# Power_Menegament.net
KiCad netlist of a schematic drawn in Altium Designer
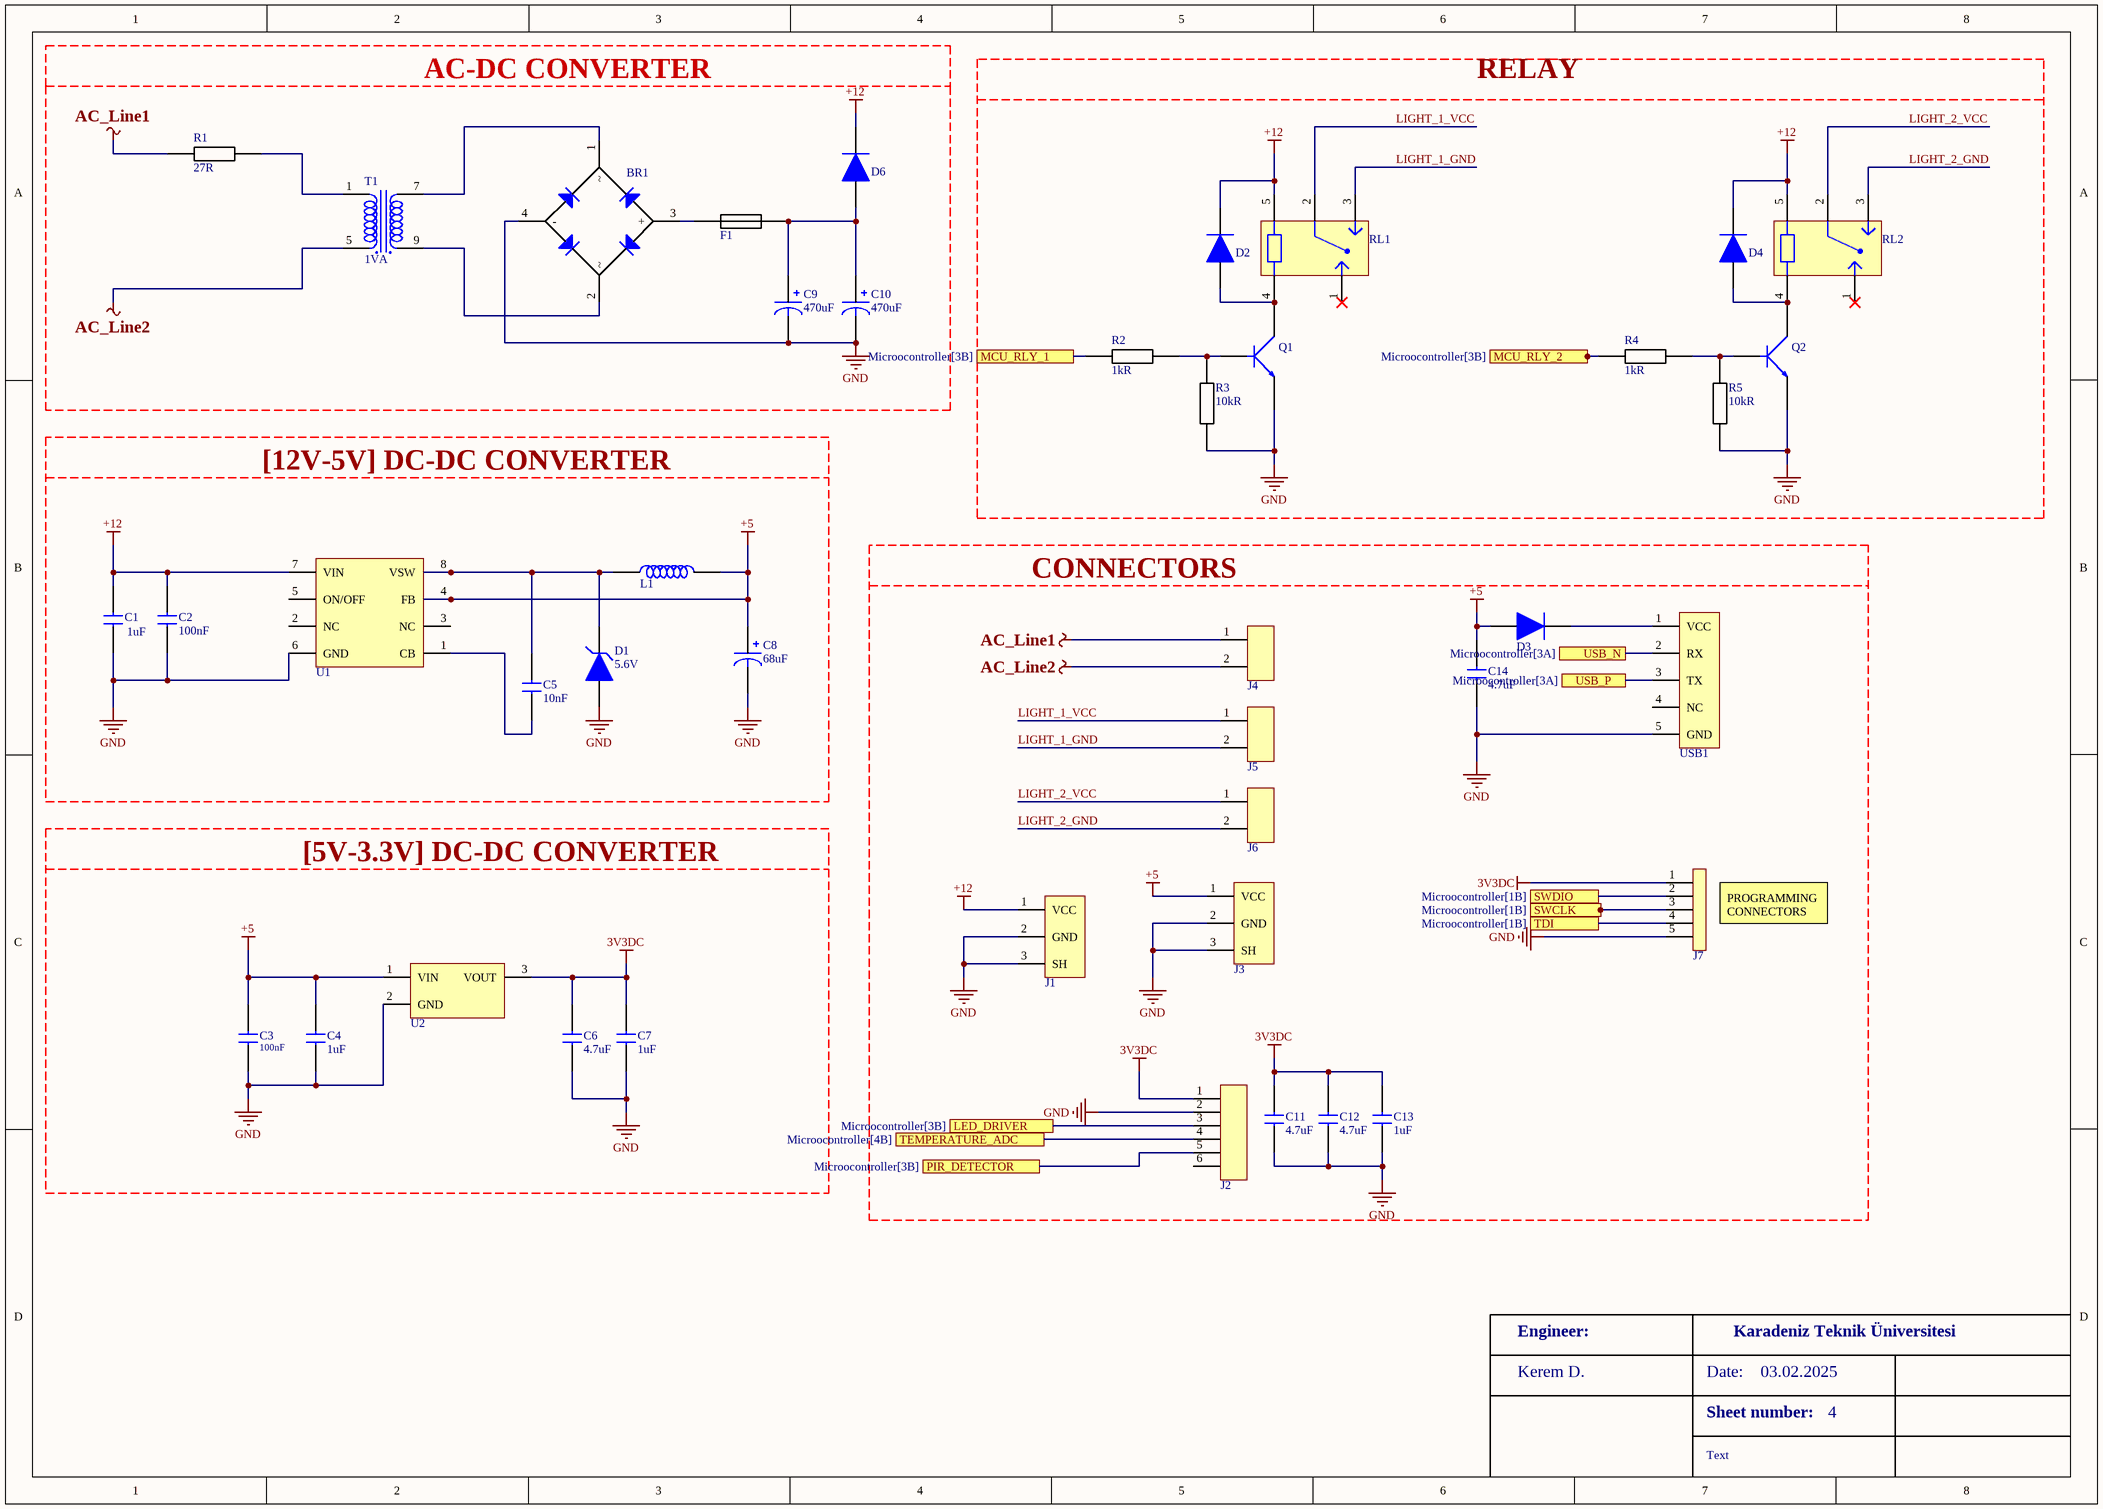
[diagram p0: Power Menegament.SchDoc]

(export (version "E")
  (design (tool "Eeschema 10.0.6"))
  (components
    (comp (ref "BR1")
      (value "DB105STR")
      (footprint "DB105STR")
      (description "Bridge Rect 1PHASE 600V 1A Db-s")
      (fields
        (field (name "MANUFACTURER") "Sangdest Microelectronics")
        (field (name "MANUFACTURER PART NUMBER") "DB105S")
        (field (name "DESIGNED BY") "Kerem")
      )
      (libsource (lib "library") (part "DB105STR"))
    )
    (comp (ref "C1")
      (value "1uF")
      (footprint "CAP_0805")
      (description "Cap CER, 1uF, 16V, 0805;")
      (fields
        (field (name "MANUFACTURER") "KEMET")
        (field (name "MANUFACTURER PART NUMBER") "CHA08C105K4RXL7189")
        (field (name "DESIGNED BY") "Kerem")
      )
      (libsource (lib "library") (part "CAP_CER_1uF_0805"))
    )
    (comp (ref "C2")
      (value "100nF")
      (footprint "CAP_0805")
      (description "Ceramic Capacitor,50V, %10, 0.1uF, Surface Mount, 0805")
      (fields
        (field (name "MANUFACTURER") "Samsung")
        (field (name "MANUFACTURER PART NUMBER") "CL21B104KBCNNNC")
        (field (name "DESIGNED BY") "Kerem")
      )
      (libsource (lib "library") (part "CAP_CER_100nF_0805"))
    )
    (comp (ref "C3")
      (value "100nF")
      (footprint "CAP_0603")
      (description "0.1 µF ±20% 50V Ceramic Capacitor X7R 0603 (1608 Metric)")
      (fields
        (field (name "MANUFACTURER") "KEMET")
        (field (name "MANUFACTURER PART NUMBER") "C0603C104M5RACTU")
      )
      (libsource (lib "library") (part "CAP CER 100nF 0603"))
    )
    (comp (ref "C4")
      (value "1uF")
      (footprint "CAP_0805")
      (description "Cap CER, 1uF, 16V, 0805;")
      (fields
        (field (name "MANUFACTURER") "KEMET")
        (field (name "MANUFACTURER PART NUMBER") "CHA08C105K4RXL7189")
        (field (name "DESIGNED BY") "Kerem")
      )
      (libsource (lib "library") (part "CAP_CER_1uF_0805"))
    )
    (comp (ref "C5")
      (value "10nF")
      (footprint "CAP_0603")
      (description "Ceramic Capacitor,16V, 10%, 0.01uF, Surface Mount, 0603")
      (fields
        (field (name "MANUFACTURER") "Walsin Technologies")
        (field (name "MANUFACTURER PART NUMBER") "0603B103K160CT")
        (field (name "DESIGNED BY") "Kerem")
      )
      (libsource (lib "library") (part "CAP_CER_10nF_0603"))
    )
    (comp (ref "C6")
      (value "4.7uF")
      (footprint "CAP_0805")
      (description "CAP CER 4.7uF,%10, Surface Mount, 0805")
      (fields
        (field (name "MANUFACTURER") "Samsung")
        (field (name "MANUFACTURER PART NUMBER") "CL21A475KAQNNNE")
        (field (name "DESIGNED BY") "Kerem")
      )
      (libsource (lib "library") (part "CAP_CER_4.7uF_0805"))
    )
    (comp (ref "C7")
      (value "1uF")
      (footprint "CAP_0805")
      (description "Cap CER, 1uF, 16V, 0805;")
      (fields
        (field (name "MANUFACTURER") "KEMET")
        (field (name "MANUFACTURER PART NUMBER") "CHA08C105K4RXL7189")
        (field (name "DESIGNED BY") "Kerem")
      )
      (libsource (lib "library") (part "CAP_CER_1uF_0805"))
    )
    (comp (ref "C8")
      (value "68uF")
      (footprint "CAP EEVSERİES")
      (description "Aluminum Electrolytic Capacitor, 35V, 20%, 68uF, Surface Mount, 2626")
      (fields
        (field (name "MANUFACTURER") "KEMET")
        (field (name "MANUFACTURER PART NUMBER") "EEV686M035A9HAA")
        (field (name "DESIGNED BY") "Kerem")
      )
      (libsource (lib "library") (part "CAP_ALU_68uF"))
    )
    (comp (ref "C9")
      (value "470uF")
      (footprint "CAP_RADİAL_D10_R5")
      (fields
        (field (name "MANUFACTURER") "KEMET")
        (field (name "MANUFACTURER PART NUMBER") "ESH477M035AH4AA")
        (field (name "DESIGNED BY") "Kerem")
      )
      (libsource (lib "library") (part "CAP_ALU_470uF"))
    )
    (comp (ref "C10")
      (value "470uF")
      (footprint "CAP_RADİAL_D10_R5")
      (fields
        (field (name "MANUFACTURER") "KEMET")
        (field (name "MANUFACTURER PART NUMBER") "ESH477M035AH4AA")
        (field (name "DESIGNED BY") "Kerem")
      )
      (libsource (lib "library") (part "CAP_ALU_470uF"))
    )
    (comp (ref "C11")
      (value "4.7uF")
      (footprint "CAP_0805")
      (description "CAP CER 4.7uF,%10, Surface Mount, 0805")
      (fields
        (field (name "MANUFACTURER") "Samsung")
        (field (name "MANUFACTURER PART NUMBER") "CL21A475KAQNNNE")
        (field (name "DESIGNED BY") "Kerem")
      )
      (libsource (lib "library") (part "CAP_CER_4.7uF_0805"))
    )
    (comp (ref "C12")
      (value "4.7uF")
      (footprint "CAP_0805")
      (description "CAP CER 4.7uF,%10, Surface Mount, 0805")
      (fields
        (field (name "MANUFACTURER") "Samsung")
        (field (name "MANUFACTURER PART NUMBER") "CL21A475KAQNNNE")
        (field (name "DESIGNED BY") "Kerem")
      )
      (libsource (lib "library") (part "CAP_CER_4.7uF_0805"))
    )
    (comp (ref "C13")
      (value "1uF")
      (footprint "CAP_0805")
      (description "Cap CER, 1uF, 16V, 0805;")
      (fields
        (field (name "MANUFACTURER") "KEMET")
        (field (name "MANUFACTURER PART NUMBER") "CHA08C105K4RXL7189")
        (field (name "DESIGNED BY") "Kerem")
      )
      (libsource (lib "library") (part "CAP_CER_1uF_0805"))
    )
    (comp (ref "C14")
      (value "4.7uF")
      (footprint "CAP_0805")
      (description "CAP CER 4.7uF,%10, Surface Mount, 0805")
      (fields
        (field (name "MANUFACTURER") "Samsung")
        (field (name "MANUFACTURER PART NUMBER") "CL21A475KAQNNNE")
        (field (name "DESIGNED BY") "Kerem")
      )
      (libsource (lib "library") (part "CAP_CER_4.7uF_0805"))
    )
    (comp (ref "D1")
      (value "1SMB5919BT3G")
      (footprint "SMB")
      (description "Zener Diode, 5.6V V(Z), 5%, 0.55W, Silicon, Unidirectional, DO-214AA")
      (fields
        (field (name "MANUFACTURER") "ON Semiconductor")
        (field (name "REFERENCE VOLTAGE-NOM") "5.6V")
        (field (name "DESIGNED BY") "Kerem")
      )
      (libsource (lib "library") (part "1SMB5919BT3G"))
    )
    (comp (ref "D2")
      (value "1N4148WS")
      (footprint "SOD323F")
      (description "Rectifier Diode, 1 Phase, 1 Element, 0.15A, 100V V(RRM), Silicon")
      (fields
        (field (name "MANUFACTURER") "ON Semiconductor / Fairchild")
        (field (name "DESIGNED BY") "Kerem")
      )
      (libsource (lib "library") (part "1N4148WS"))
    )
    (comp (ref "D3")
      (value "1N4148WS")
      (footprint "SOD323F")
      (description "Rectifier Diode, 1 Phase, 1 Element, 0.15A, 100V V(RRM), Silicon")
      (fields
        (field (name "MANUFACTURER") "ON Semiconductor / Fairchild")
        (field (name "DESIGNED BY") "Kerem")
      )
      (libsource (lib "library") (part "1N4148WS"))
    )
    (comp (ref "D4")
      (value "1N4148WS")
      (footprint "SOD323F")
      (description "Rectifier Diode, 1 Phase, 1 Element, 0.15A, 100V V(RRM), Silicon")
      (fields
        (field (name "MANUFACTURER") "ON Semiconductor / Fairchild")
        (field (name "DESIGNED BY") "Kerem")
      )
      (libsource (lib "library") (part "1N4148WS"))
    )
    (comp (ref "D6")
      (value "1N4148WS")
      (footprint "SOD323F")
      (description "Rectifier Diode, 1 Phase, 1 Element, 0.15A, 100V V(RRM), Silicon")
      (fields
        (field (name "MANUFACTURER") "ON Semiconductor / Fairchild")
        (field (name "DESIGNED BY") "Kerem")
      )
      (libsource (lib "library") (part "1N4148WS"))
    )
    (comp (ref "F1")
      (value "3413.0216.22")
      (footprint "FUSE 3413.0216.22")
      (description "Electric Fuse, Very Fast Blow, 1A, 32VAC, 63VDC, 63A (IR), Surface Mount, 1206")
      (fields (field (name "MANUFACTURER") "Schurter") (field (name "DESIGNED BY") "Kerem"))
      (libsource (lib "library") (part "FUSE 3413.0216.22"))
    )
    (comp (ref "J1")
      (value "JACK")
      (footprint "JACK")
      (description "DC Power Plug or Jack")
      (fields
        (field (name "MANUFACTURER") "CUI")
        (field (name "MANUFACTURER PART NUMBER") "PJ-037AH-SMT-TR")
        (field (name "DESIGNED BY") "Kerem")
      )
      (libsource (lib "library") (part "PJ-037AH-SMT-TR"))
    )
    (comp (ref "J2")
      (value "64800611622")
      (footprint "64800611622")
      (description "WR-WTB Wire-to-Board Connectors 1.50 mm")
      (fields (field (name "MANUFACTURER") "Wurth Electronics") (field (name "DESIGNED BY") "Kerem"))
      (libsource (lib "library") (part "64800611622_CONN_6PINS"))
    )
    (comp (ref "J3")
      (value "JACK")
      (footprint "JACK")
      (description "DC Power Plug or Jack")
      (fields
        (field (name "MANUFACTURER") "CUI")
        (field (name "MANUFACTURER PART NUMBER") "PJ-037AH-SMT-TR")
        (field (name "DESIGNED BY") "Kerem")
      )
      (libsource (lib "library") (part "PJ-037AH-SMT-TR"))
    )
    (comp (ref "J4")
      (value "JACK")
      (footprint "TBP01R1-508")
      (description "Strip Terminal Block 2 Pins")
      (fields
        (field (name "MANUFACTURER") "CUI Devices")
        (field (name "MANUFACTURER PART NUMBER") "TBP01R1-508-02BE")
        (field (name "DESIGNED BY") "Kerem")
      )
      (libsource (lib "library") (part "TBP01R1-508-02BE"))
    )
    (comp (ref "J5")
      (value "JACK")
      (footprint "TBP01R1-508")
      (description "Strip Terminal Block 2 Pins")
      (fields
        (field (name "MANUFACTURER") "CUI Devices")
        (field (name "MANUFACTURER PART NUMBER") "TBP01R1-508-02BE")
        (field (name "DESIGNED BY") "Kerem")
      )
      (libsource (lib "library") (part "TBP01R1-508-02BE"))
    )
    (comp (ref "J6")
      (value "JACK")
      (footprint "TBP01R1-508")
      (description "Strip Terminal Block 2 Pins")
      (fields
        (field (name "MANUFACTURER") "CUI Devices")
        (field (name "MANUFACTURER PART NUMBER") "TBP01R1-508-02BE")
        (field (name "DESIGNED BY") "Kerem")
      )
      (libsource (lib "library") (part "TBP01R1-508-02BE"))
    )
    (comp (ref "J7")
      (value "SMH-105-02-L-S")
      (footprint "PINHEADER1X5_RA")
      (description "Board Connector, 5 Contact(s), Socket")
      (fields (field (name "MANUFACTURER") "Samtec") (field (name "DESIGNED BY") "Kerem"))
      (libsource (lib "library") (part "SMH-105-02-L-S"))
    )
    (comp (ref "L1")
      (value "78438335470")
      (footprint "SMB")
      (description "General Purpose Inductor, 47uH, 20%, 1 Element, Iron Alloy-Core, SMD, 1212")
      (fields (field (name "MANUFACTURER") "Wurth Electronics") (field (name "DESIGNED BY") "Kerem"))
      (libsource (lib "library") (part "IND_47uH"))
    )
    (comp (ref "Q1")
      (value "MMBT3904-7-F")
      (footprint "SOT-23F")
      (description "Small Signal Bipolar Transistor, 0.2A I(C), 40V V(BR)CEO, 1-Element, NPN, Silicon")
      (fields (field (name "MANUFACTURER") "Diodes Zetex") (field (name "DESIGNED BY") "Kerem"))
      (libsource (lib "library") (part "MMBT3904-7-F"))
    )
    (comp (ref "Q2")
      (value "MMBT3904-7-F")
      (footprint "SOT-23F")
      (description "Small Signal Bipolar Transistor, 0.2A I(C), 40V V(BR)CEO, 1-Element, NPN, Silicon")
      (fields (field (name "MANUFACTURER") "Diodes Zetex") (field (name "DESIGNED BY") "Kerem"))
      (libsource (lib "library") (part "MMBT3904-7-F"))
    )
    (comp (ref "R1")
      (value "27R")
      (footprint "RES_AXIAL_W")
      (description "5W, 27ohm, 350V, 5% Through Hole Mount, 8739")
      (fields
        (field (name "MANUFACTURER") "TE Connectivity CGS")
        (field (name "MANUFACTURER PART NUMBER") "SQPW527RJ")
        (field (name "DESIGNED BY") "Kerem")
      )
      (libsource (lib "library") (part "5WD27"))
    )
    (comp (ref "R2")
      (value "1kR")
      (footprint "RES_0603")
      (description "0.1W, 1000ohm, 75V, 5%, Surface Mount, 0603")
      (fields
        (field (name "MANUFACTURER") "Yageo")
        (field (name "MANUFACTURER PART NUMBER") "RC0603JR-071KL")
        (field (name "DESIGNED BY") "Kerem")
      )
      (libsource (lib "library") (part "RES_1K OHM_0603"))
    )
    (comp (ref "R3")
      (value "10kR")
      (footprint "RES_0603")
      (fields
        (field (name "MANUFACTURER") "Yageo")
        (field (name "MANUFACTURER PART NUMBER") "RC0603FR-0710KL")
        (field (name "TOLERANCE") "1%")
        (field (name "DESIGNED BY") "Kerem")
      )
      (libsource (lib "library") (part "RES 10K OHM 0603"))
    )
    (comp (ref "R4")
      (value "1kR")
      (footprint "RES_0603")
      (description "0.1W, 1000ohm, 75V, 5%, Surface Mount, 0603")
      (fields
        (field (name "MANUFACTURER") "Yageo")
        (field (name "MANUFACTURER PART NUMBER") "RC0603JR-071KL")
        (field (name "DESIGNED BY") "Kerem")
      )
      (libsource (lib "library") (part "RES_1K OHM_0603"))
    )
    (comp (ref "R5")
      (value "10kR")
      (footprint "RES_0603")
      (fields
        (field (name "MANUFACTURER") "Yageo")
        (field (name "MANUFACTURER PART NUMBER") "RC0603FR-0710KL")
        (field (name "TOLERANCE") "1%")
        (field (name "DESIGNED BY") "Kerem")
      )
      (libsource (lib "library") (part "RES 10K OHM 0603"))
    )
    (comp (ref "RL1")
      (value "ALQ112")
      (footprint "ALQ112")
      (fields (field (name "MANUFACTURER") "Panasonic") (field (name "DESIGNED BY") "Kerem"))
      (libsource (lib "library") (part "ALQ112"))
    )
    (comp (ref "RL2")
      (value "ALQ112")
      (footprint "ALQ112")
      (fields (field (name "MANUFACTURER") "Panasonic") (field (name "DESIGNED BY") "Kerem"))
      (libsource (lib "library") (part "ALQ112"))
    )
    (comp (ref "T1")
      (value "BV302S12010-ZU")
      (footprint "BV302S12010-ZU")
      (description "Split Bobbin Power Transformer, 1VA")
      (fields
        (field (name "MANUFACTURER") "Zettler Magnetics")
        (field (name "MANUFACTURER PART NUMBER") "BV302S12010")
        (field (name "POWER - MAX") "1VA")
        (field (name "DESIGNED BY") "Kerem")
      )
      (libsource (lib "library") (part "BV302S12010-ZU"))
    )
    (comp (ref "U1")
      (value "LM2675MX-12/NOPB")
      (footprint "SOIC8")
      (description "Switching Regulator, Voltage-mode, 2.2A, 275kHz Switching Freq-Max, DMOS, PDSO8")
      (fields (field (name "MANUFACTURER") "TI National Semiconductor") (field (name "DESIGNED BY") "Kerem"))
      (libsource (lib "library") (part "LM2675MX-12/NOPB"))
    )
    (comp (ref "U2")
      (value "AP7361-33E-13")
      (footprint "SOT223")
      (description "Fixed Positive LDO Regulator, 3.3V, 0.7V Dropout, CMOS, PSSO3")
      (fields (field (name "MANUFACTURER") "Diodes") (field (name "DESIGNED BY") "Kerem"))
      (libsource (lib "library") (part "AP7361-33E-13"))
    )
    (comp (ref "USB1")
      (value "10118192-0001LF")
      (footprint "Micro_B_USB")
      (description "CONN USB MICRO B RECPT SMT R/A")
      (fields (field (name "MANUFACTURER") "Amphenol ICC / FCI") (field (name "DESIGNED BY") "Kerem"))
      (libsource (lib "library") (part "Micro B USB Connector"))
    )
  )
  (nets
    (net (code "1") (name "+5") (class "Default")
      (node (ref "C14") (pin "2") (pinfunction "2_2") (pintype "passive"))
      (node (ref "C3") (pin "2") (pinfunction "2_2") (pintype "passive"))
      (node (ref "C4") (pin "2") (pinfunction "2_2") (pintype "passive"))
      (node (ref "C8") (pin "1") (pinfunction "1_1") (pintype "passive"))
      (node (ref "D3") (pin "2") (pinfunction "2_2") (pintype "passive"))
      (node (ref "J3") (pin "1") (pinfunction "VCC_1") (pintype "power_in"))
      (node (ref "L1") (pin "2") (pinfunction "2_2") (pintype "passive"))
      (node (ref "U1") (pin "4") (pinfunction "FB_4") (pintype "passive"))
      (node (ref "U2") (pin "1") (pinfunction "VIN_1") (pintype "passive"))
    )
    (net (code "2") (name "+12") (class "Default")
      (node (ref "C1") (pin "2") (pinfunction "2_2") (pintype "passive"))
      (node (ref "C2") (pin "2") (pinfunction "2_2") (pintype "passive"))
      (node (ref "D2") (pin "1") (pinfunction "1_1") (pintype "passive"))
      (node (ref "D4") (pin "1") (pinfunction "1_1") (pintype "passive"))
      (node (ref "D6") (pin "1") (pinfunction "1_1") (pintype "passive"))
      (node (ref "J1") (pin "1") (pinfunction "VCC_1") (pintype "power_in"))
      (node (ref "RL1") (pin "5") (pintype "passive"))
      (node (ref "RL2") (pin "5") (pintype "passive"))
      (node (ref "U1") (pin "7") (pinfunction "VIN_7") (pintype "passive"))
    )
    (net (code "4") (name "/LED_DRIVER") (class "Default")
      (node (ref "J2") (pin "3") (pinfunction "3_3") (pintype "passive"))
    )
    (net (code "5") (name "/LIGHT_1_GND") (class "Default")
      (node (ref "J5") (pin "2") (pinfunction "2_2") (pintype "power_in"))
      (node (ref "RL1") (pin "3") (pintype "passive"))
    )
    (net (code "6") (name "/LIGHT_1_VCC") (class "Default")
      (node (ref "J5") (pin "1") (pinfunction "1_1") (pintype "power_in"))
      (node (ref "RL1") (pin "2") (pintype "passive"))
    )
    (net (code "7") (name "/LIGHT_2_GND") (class "Default")
      (node (ref "J6") (pin "2") (pinfunction "2_2") (pintype "power_in"))
      (node (ref "RL2") (pin "3") (pintype "passive"))
    )
    (net (code "8") (name "/LIGHT_2_VCC") (class "Default")
      (node (ref "J6") (pin "1") (pinfunction "1_1") (pintype "power_in"))
      (node (ref "RL2") (pin "2") (pintype "passive"))
    )
    (net (code "9") (name "/MCU_RLY_1") (class "Default")
      (node (ref "R2") (pin "1") (pinfunction "1_1") (pintype "passive"))
    )
    (net (code "10") (name "/MCU_RLY_2") (class "Default")
      (node (ref "R4") (pin "1") (pinfunction "1_1") (pintype "passive"))
    )
    (net (code "11") (name "/PIR_DETECTOR") (class "Default")
      (node (ref "J2") (pin "5") (pinfunction "5_5") (pintype "passive"))
    )
    (net (code "12") (name "/SWCLK") (class "Default")
      (node (ref "J7") (pin "3") (pinfunction "3_3") (pintype "power_in"))
    )
    (net (code "13") (name "/SWDIO") (class "Default")
      (node (ref "J7") (pin "2") (pinfunction "2_2") (pintype "power_in"))
    )
    (net (code "14") (name "/TDI") (class "Default")
      (node (ref "J7") (pin "4") (pinfunction "4_4") (pintype "power_in"))
    )
    (net (code "15") (name "/TEMPERATURE_ADC") (class "Default")
      (node (ref "J2") (pin "4") (pinfunction "4_4") (pintype "passive"))
    )
    (net (code "16") (name "/USB_N") (class "Default")
      (node (ref "USB1") (pin "2") (pinfunction "RX_2") (pintype "passive"))
    )
    (net (code "17") (name "/USB_P") (class "Default")
      (node (ref "USB1") (pin "3") (pinfunction "TX_3") (pintype "passive"))
    )
    (net (code "18") (name "3V3DC") (class "Default")
      (node (ref "C11") (pin "2") (pinfunction "2_2") (pintype "passive"))
      (node (ref "C12") (pin "2") (pinfunction "2_2") (pintype "passive"))
      (node (ref "C13") (pin "2") (pinfunction "2_2") (pintype "passive"))
      (node (ref "C6") (pin "2") (pinfunction "2_2") (pintype "passive"))
      (node (ref "C7") (pin "2") (pinfunction "2_2") (pintype "passive"))
      (node (ref "J2") (pin "1") (pinfunction "1_1") (pintype "passive"))
      (node (ref "J7") (pin "1") (pinfunction "1_1") (pintype "power_in"))
      (node (ref "U2") (pin "3") (pinfunction "VOUT_3") (pintype "passive"))
    )
    (net (code "19") (name "AC_Line1") (class "Default")
      (node (ref "J4") (pin "1") (pinfunction "1_1") (pintype "power_in"))
      (node (ref "R1") (pin "1") (pinfunction "1_1") (pintype "passive"))
    )
    (net (code "20") (name "AC_Line2") (class "Default")
      (node (ref "J4") (pin "2") (pinfunction "2_2") (pintype "power_in"))
      (node (ref "T1") (pin "5") (pinfunction "2_5") (pintype "passive"))
    )
    (net (code "21") (name "GND") (class "Default")
      (node (ref "BR1") (pin "4") (pinfunction "-_4") (pintype "passive"))
      (node (ref "C1") (pin "1") (pinfunction "1_1") (pintype "passive"))
      (node (ref "C10") (pin "2") (pinfunction "2_2") (pintype "passive"))
      (node (ref "C11") (pin "1") (pinfunction "1_1") (pintype "passive"))
      (node (ref "C12") (pin "1") (pinfunction "1_1") (pintype "passive"))
      (node (ref "C13") (pin "1") (pinfunction "1_1") (pintype "passive"))
      (node (ref "C14") (pin "1") (pinfunction "1_1") (pintype "passive"))
      (node (ref "C2") (pin "1") (pinfunction "1_1") (pintype "passive"))
      (node (ref "C3") (pin "1") (pinfunction "1_1") (pintype "passive"))
      (node (ref "C4") (pin "1") (pinfunction "1_1") (pintype "passive"))
      (node (ref "C6") (pin "1") (pinfunction "1_1") (pintype "passive"))
      (node (ref "C7") (pin "1") (pinfunction "1_1") (pintype "passive"))
      (node (ref "C8") (pin "2") (pinfunction "2_2") (pintype "passive"))
      (node (ref "C9") (pin "2") (pinfunction "2_2") (pintype "passive"))
      (node (ref "D1") (pin "1") (pinfunction "A_1") (pintype "passive"))
      (node (ref "J1") (pin "2") (pinfunction "GND_2") (pintype "power_in"))
      (node (ref "J1") (pin "3") (pinfunction "SH_3") (pintype "power_in"))
      (node (ref "J2") (pin "2") (pinfunction "2_2") (pintype "passive"))
      (node (ref "J3") (pin "2") (pinfunction "GND_2") (pintype "power_in"))
      (node (ref "J3") (pin "3") (pinfunction "SH_3") (pintype "power_in"))
      (node (ref "J7") (pin "5") (pinfunction "5_5") (pintype "power_in"))
      (node (ref "Q1") (pin "2") (pinfunction "E_2") (pintype "passive"))
      (node (ref "Q2") (pin "2") (pinfunction "E_2") (pintype "passive"))
      (node (ref "R3") (pin "1") (pinfunction "1_1") (pintype "passive"))
      (node (ref "R5") (pin "1") (pinfunction "1_1") (pintype "passive"))
      (node (ref "U1") (pin "6") (pinfunction "GND_6") (pintype "passive"))
      (node (ref "U2") (pin "2") (pinfunction "GND_2") (pintype "passive"))
      (node (ref "USB1") (pin "5") (pinfunction "GND_5") (pintype "passive"))
    )
    (net (code "22") (name "Net-(BR1-+)") (class "Default")
      (node (ref "BR1") (pin "3") (pinfunction "+_3") (pintype "passive"))
      (node (ref "F1") (pin "1") (pinfunction "1_1") (pintype "passive"))
    )
    (net (code "23") (name "Net-(C10-Pad1)") (class "Default")
      (node (ref "C10") (pin "1") (pinfunction "1_1") (pintype "passive"))
      (node (ref "C9") (pin "1") (pinfunction "1_1") (pintype "passive"))
      (node (ref "D6") (pin "2") (pinfunction "2_2") (pintype "passive"))
      (node (ref "F1") (pin "2") (pinfunction "2_2") (pintype "passive"))
    )
    (net (code "24") (name "Net-(D1-C)") (class "Default")
      (node (ref "C5") (pin "2") (pinfunction "2_2") (pintype "passive"))
      (node (ref "D1") (pin "2") (pinfunction "C_2") (pintype "passive"))
      (node (ref "L1") (pin "1") (pinfunction "1_1") (pintype "passive"))
      (node (ref "U1") (pin "8") (pinfunction "VSW_8") (pintype "passive"))
    )
    (net (code "25") (name "Net-(Q1-B)") (class "Default")
      (node (ref "Q1") (pin "1") (pinfunction "B_1") (pintype "passive"))
      (node (ref "R2") (pin "2") (pinfunction "2_2") (pintype "passive"))
      (node (ref "R3") (pin "2") (pinfunction "2_2") (pintype "passive"))
    )
    (net (code "26") (name "Net-(Q1-C)") (class "Default")
      (node (ref "D2") (pin "2") (pinfunction "2_2") (pintype "passive"))
      (node (ref "Q1") (pin "3") (pinfunction "C_3") (pintype "passive"))
      (node (ref "RL1") (pin "4") (pintype "passive"))
    )
    (net (code "27") (name "Net-(Q2-B)") (class "Default")
      (node (ref "Q2") (pin "1") (pinfunction "B_1") (pintype "passive"))
      (node (ref "R4") (pin "2") (pinfunction "2_2") (pintype "passive"))
      (node (ref "R5") (pin "2") (pinfunction "2_2") (pintype "passive"))
    )
    (net (code "28") (name "Net-(Q2-C)") (class "Default")
      (node (ref "D4") (pin "2") (pinfunction "2_2") (pintype "passive"))
      (node (ref "Q2") (pin "3") (pinfunction "C_3") (pintype "passive"))
      (node (ref "RL2") (pin "4") (pintype "passive"))
    )
    (net (code "29") (name "Net-(R1-Pad2)") (class "Default")
      (node (ref "R1") (pin "2") (pinfunction "2_2") (pintype "passive"))
      (node (ref "T1") (pin "1") (pinfunction "1_1") (pintype "passive"))
    )
    (net (code "30") (name "Net-(T1-3)") (class "Default")
      (node (ref "BR1") (pin "1") (pinfunction "~_1") (pintype "passive"))
      (node (ref "T1") (pin "7") (pinfunction "3_7") (pintype "passive"))
    )
    (net (code "31") (name "Net-(T1-4)") (class "Default")
      (node (ref "BR1") (pin "2") (pinfunction "~_2") (pintype "passive"))
      (node (ref "T1") (pin "9") (pinfunction "4_9") (pintype "passive"))
    )
    (net (code "32") (name "Net-(U1-CB)") (class "Default")
      (node (ref "C5") (pin "1") (pinfunction "1_1") (pintype "passive"))
      (node (ref "U1") (pin "1") (pinfunction "CB_1") (pintype "passive"))
    )
    (net (code "33") (name "Net-(USB1-VCC)") (class "Default")
      (node (ref "D3") (pin "1") (pinfunction "1_1") (pintype "passive"))
      (node (ref "USB1") (pin "1") (pinfunction "VCC_1") (pintype "passive"))
    )
    (net (code "34") (name "unconnected-(J2-Pad6)") (class "Default")
      (node (ref "J2") (pin "6") (pinfunction "6_6") (pintype "passive"))
    )
    (net (code "35") (name "unconnected-(RL1-+-Pad1)") (class "Default")
      (node (ref "RL1") (pin "1") (pinfunction "+_1") (pintype "passive+no_connect"))
    )
    (net (code "36") (name "unconnected-(RL2-+-Pad1)") (class "Default")
      (node (ref "RL2") (pin "1") (pinfunction "+_1") (pintype "passive+no_connect"))
    )
    (net (code "37") (name "unconnected-(U1-NC-Pad2)") (class "Default")
      (node (ref "U1") (pin "2") (pinfunction "NC_2") (pintype "passive"))
    )
    (net (code "38") (name "unconnected-(U1-NC-Pad3)") (class "Default")
      (node (ref "U1") (pin "3") (pinfunction "NC_3") (pintype "passive"))
    )
    (net (code "39") (name "unconnected-(U1-ON{slash}OFF-Pad5)") (class "Default")
      (node (ref "U1") (pin "5") (pinfunction "ON/OFF_5") (pintype "passive"))
    )
    (net (code "40") (name "unconnected-(USB1-NC-Pad4)") (class "Default")
      (node (ref "USB1") (pin "4") (pinfunction "NC_4") (pintype "passive"))
    )
  )
)
